# breakout_noxtal_4.net
KiCad netlist of a schematic drawn in EAGLE
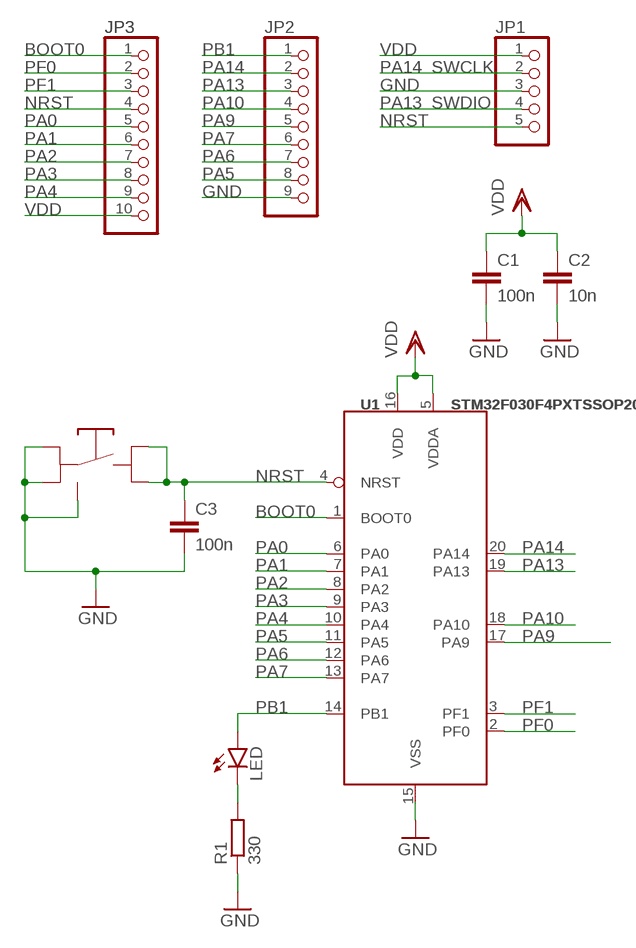
[diagram p0: schematic, sheet 1]

(export (version "E")
  (design (tool "Eeschema 10.0.6"))
  (components
    (comp (ref "C1")
      (value "100n")
      (footprint "eagle-import:C0603")
      (libsource (lib "eagle-import") (part "C-EUC0603"))
    )
    (comp (ref "C2")
      (value "10n")
      (footprint "eagle-import:C0603")
      (libsource (lib "eagle-import") (part "C-EUC0603"))
    )
    (comp (ref "C3")
      (value "100n")
      (footprint "eagle-import:C0603")
      (libsource (lib "eagle-import") (part "C-EUC0603"))
    )
    (comp (ref "JP1")
      (value "PINHD-1X5/90")
      (footprint "eagle-import:1X05_90")
      (libsource (lib "eagle-import") (part "PINHD-1X5/90"))
    )
    (comp (ref "JP2")
      (value "PINHD-1X9")
      (footprint "eagle-import:1X09")
      (libsource (lib "eagle-import") (part "PINHD-1X9"))
    )
    (comp (ref "JP3")
      (value "PINHD-1X10")
      (footprint "eagle-import:1X10")
      (libsource (lib "eagle-import") (part "PINHD-1X10"))
    )
    (comp (ref "LED")
      (value "LED")
      (footprint "eagle-import:LED-0603-CR")
      (libsource (lib "eagle-import") (part "LED"))
    )
    (comp (ref "R1")
      (value "330")
      (footprint "eagle-import:R0603")
      (libsource (lib "eagle-import") (part "R-EUR0603"))
    )
    (comp (ref "RESET")
      (value "KMR2XXG")
      (footprint "eagle-import:KMR2XXG")
      (libsource (lib "eagle-import") (part "KMR2XXG"))
    )
    (comp (ref "U1")
      (value "STM32F030F4PXTSSOP20")
      (footprint "eagle-import:STM32F030F4PX_TSSOP20")
      (libsource (lib "eagle-import") (part "STM32F030F4PXTSSOP20"))
    )
  )
  (nets
    (net (code "1") (name "/BOOT0") (class "Default")
      (node (ref "JP3") (pin "1") (pinfunction "1_1") (pintype "passive"))
      (node (ref "U1") (pin "1") (pinfunction "BOOT0_1") (pintype "input"))
    )
    (net (code "2") (name "/NRST") (class "Default")
      (node (ref "C3") (pin "1") (pinfunction "1_1") (pintype "passive"))
      (node (ref "JP1") (pin "5") (pinfunction "5_5") (pintype "passive"))
      (node (ref "JP3") (pin "4") (pinfunction "4_4") (pintype "passive"))
      (node (ref "RESET") (pin "P$1") (pinfunction "1_P$1") (pintype "bidirectional"))
      (node (ref "RESET") (pin "P$2") (pinfunction "2_P$2") (pintype "bidirectional"))
      (node (ref "U1") (pin "4") (pinfunction "NRST_4") (pintype "input"))
    )
    (net (code "3") (name "/PA0") (class "Default")
      (node (ref "JP3") (pin "5") (pinfunction "5_5") (pintype "passive"))
      (node (ref "U1") (pin "6") (pinfunction "PA0_6") (pintype "bidirectional"))
    )
    (net (code "4") (name "/PA1") (class "Default")
      (node (ref "JP3") (pin "6") (pinfunction "6_6") (pintype "passive"))
      (node (ref "U1") (pin "7") (pinfunction "PA1_7") (pintype "bidirectional"))
    )
    (net (code "5") (name "/PA2") (class "Default")
      (node (ref "JP3") (pin "7") (pinfunction "7_7") (pintype "passive"))
      (node (ref "U1") (pin "8") (pinfunction "PA2_8") (pintype "bidirectional"))
    )
    (net (code "6") (name "/PA3") (class "Default")
      (node (ref "JP3") (pin "8") (pinfunction "8_8") (pintype "passive"))
      (node (ref "U1") (pin "9") (pinfunction "PA3_9") (pintype "bidirectional"))
    )
    (net (code "7") (name "/PA4") (class "Default")
      (node (ref "JP3") (pin "9") (pinfunction "9_9") (pintype "passive"))
      (node (ref "U1") (pin "10") (pinfunction "PA4_10") (pintype "bidirectional"))
    )
    (net (code "8") (name "/PA5") (class "Default")
      (node (ref "JP2") (pin "8") (pinfunction "8_8") (pintype "passive"))
      (node (ref "U1") (pin "11") (pinfunction "PA5_11") (pintype "bidirectional"))
    )
    (net (code "9") (name "/PA6") (class "Default")
      (node (ref "JP2") (pin "7") (pinfunction "7_7") (pintype "passive"))
      (node (ref "U1") (pin "12") (pinfunction "PA6_12") (pintype "bidirectional"))
    )
    (net (code "10") (name "/PA7") (class "Default")
      (node (ref "JP2") (pin "6") (pinfunction "6_6") (pintype "passive"))
      (node (ref "U1") (pin "13") (pinfunction "PA7_13") (pintype "bidirectional"))
    )
    (net (code "11") (name "/PA9") (class "Default")
      (node (ref "JP2") (pin "5") (pinfunction "5_5") (pintype "passive"))
      (node (ref "U1") (pin "17") (pinfunction "PA9_17") (pintype "bidirectional"))
    )
    (net (code "12") (name "/PA10") (class "Default")
      (node (ref "JP2") (pin "4") (pinfunction "4_4") (pintype "passive"))
      (node (ref "U1") (pin "18") (pinfunction "PA10_18") (pintype "bidirectional"))
    )
    (net (code "13") (name "/PA13") (class "Default")
      (node (ref "JP1") (pin "4") (pinfunction "4_4") (pintype "passive"))
      (node (ref "JP2") (pin "3") (pinfunction "3_3") (pintype "passive"))
      (node (ref "U1") (pin "19") (pinfunction "PA13_19") (pintype "bidirectional"))
    )
    (net (code "14") (name "/PA14") (class "Default")
      (node (ref "JP1") (pin "2") (pinfunction "2_2") (pintype "passive"))
      (node (ref "JP2") (pin "2") (pinfunction "2_2") (pintype "passive"))
      (node (ref "U1") (pin "20") (pinfunction "PA14_20") (pintype "bidirectional"))
    )
    (net (code "15") (name "/PB1") (class "Default")
      (node (ref "JP2") (pin "1") (pinfunction "1_1") (pintype "passive"))
      (node (ref "LED") (pin "2") (pinfunction "A_2") (pintype "passive"))
      (node (ref "U1") (pin "14") (pinfunction "PB1_14") (pintype "bidirectional"))
    )
    (net (code "16") (name "/PF0") (class "Default")
      (node (ref "JP3") (pin "2") (pinfunction "2_2") (pintype "passive"))
      (node (ref "U1") (pin "2") (pinfunction "PF0_2") (pintype "bidirectional"))
    )
    (net (code "17") (name "/PF1") (class "Default")
      (node (ref "JP3") (pin "3") (pinfunction "3_3") (pintype "passive"))
      (node (ref "U1") (pin "3") (pinfunction "PF1_3") (pintype "bidirectional"))
    )
    (net (code "18") (name "GND") (class "Default")
      (node (ref "C1") (pin "2") (pinfunction "2_2") (pintype "passive"))
      (node (ref "C2") (pin "2") (pinfunction "2_2") (pintype "passive"))
      (node (ref "C3") (pin "2") (pinfunction "2_2") (pintype "passive"))
      (node (ref "JP1") (pin "3") (pinfunction "3_3") (pintype "passive"))
      (node (ref "JP2") (pin "9") (pinfunction "9_9") (pintype "passive"))
      (node (ref "R1") (pin "1") (pinfunction "1_1") (pintype "passive"))
      (node (ref "RESET") (pin "P$3") (pinfunction "3_P$3") (pintype "bidirectional"))
      (node (ref "RESET") (pin "P$4") (pinfunction "4_P$4") (pintype "bidirectional"))
      (node (ref "RESET") (pin "P$5") (pinfunction "G_P$5") (pintype "bidirectional"))
      (node (ref "U1") (pin "15") (pinfunction "VSS_15") (pintype "power_in"))
    )
    (net (code "19") (name "Net-(LED-C)") (class "Default")
      (node (ref "LED") (pin "1") (pinfunction "C_1") (pintype "passive"))
      (node (ref "R1") (pin "2") (pinfunction "2_2") (pintype "passive"))
    )
    (net (code "20") (name "VDD") (class "Default")
      (node (ref "C1") (pin "1") (pinfunction "1_1") (pintype "passive"))
      (node (ref "C2") (pin "1") (pinfunction "1_1") (pintype "passive"))
      (node (ref "JP1") (pin "1") (pinfunction "1_1") (pintype "passive"))
      (node (ref "JP3") (pin "10") (pinfunction "10_10") (pintype "passive"))
      (node (ref "U1") (pin "16") (pinfunction "VDD_16") (pintype "power_in"))
      (node (ref "U1") (pin "5") (pinfunction "VDDA_5") (pintype "power_in"))
    )
  )
)
